# Ctrl_Sist_de_seguridad_SCH.net
KiCad netlist of a schematic drawn in Altium Designer
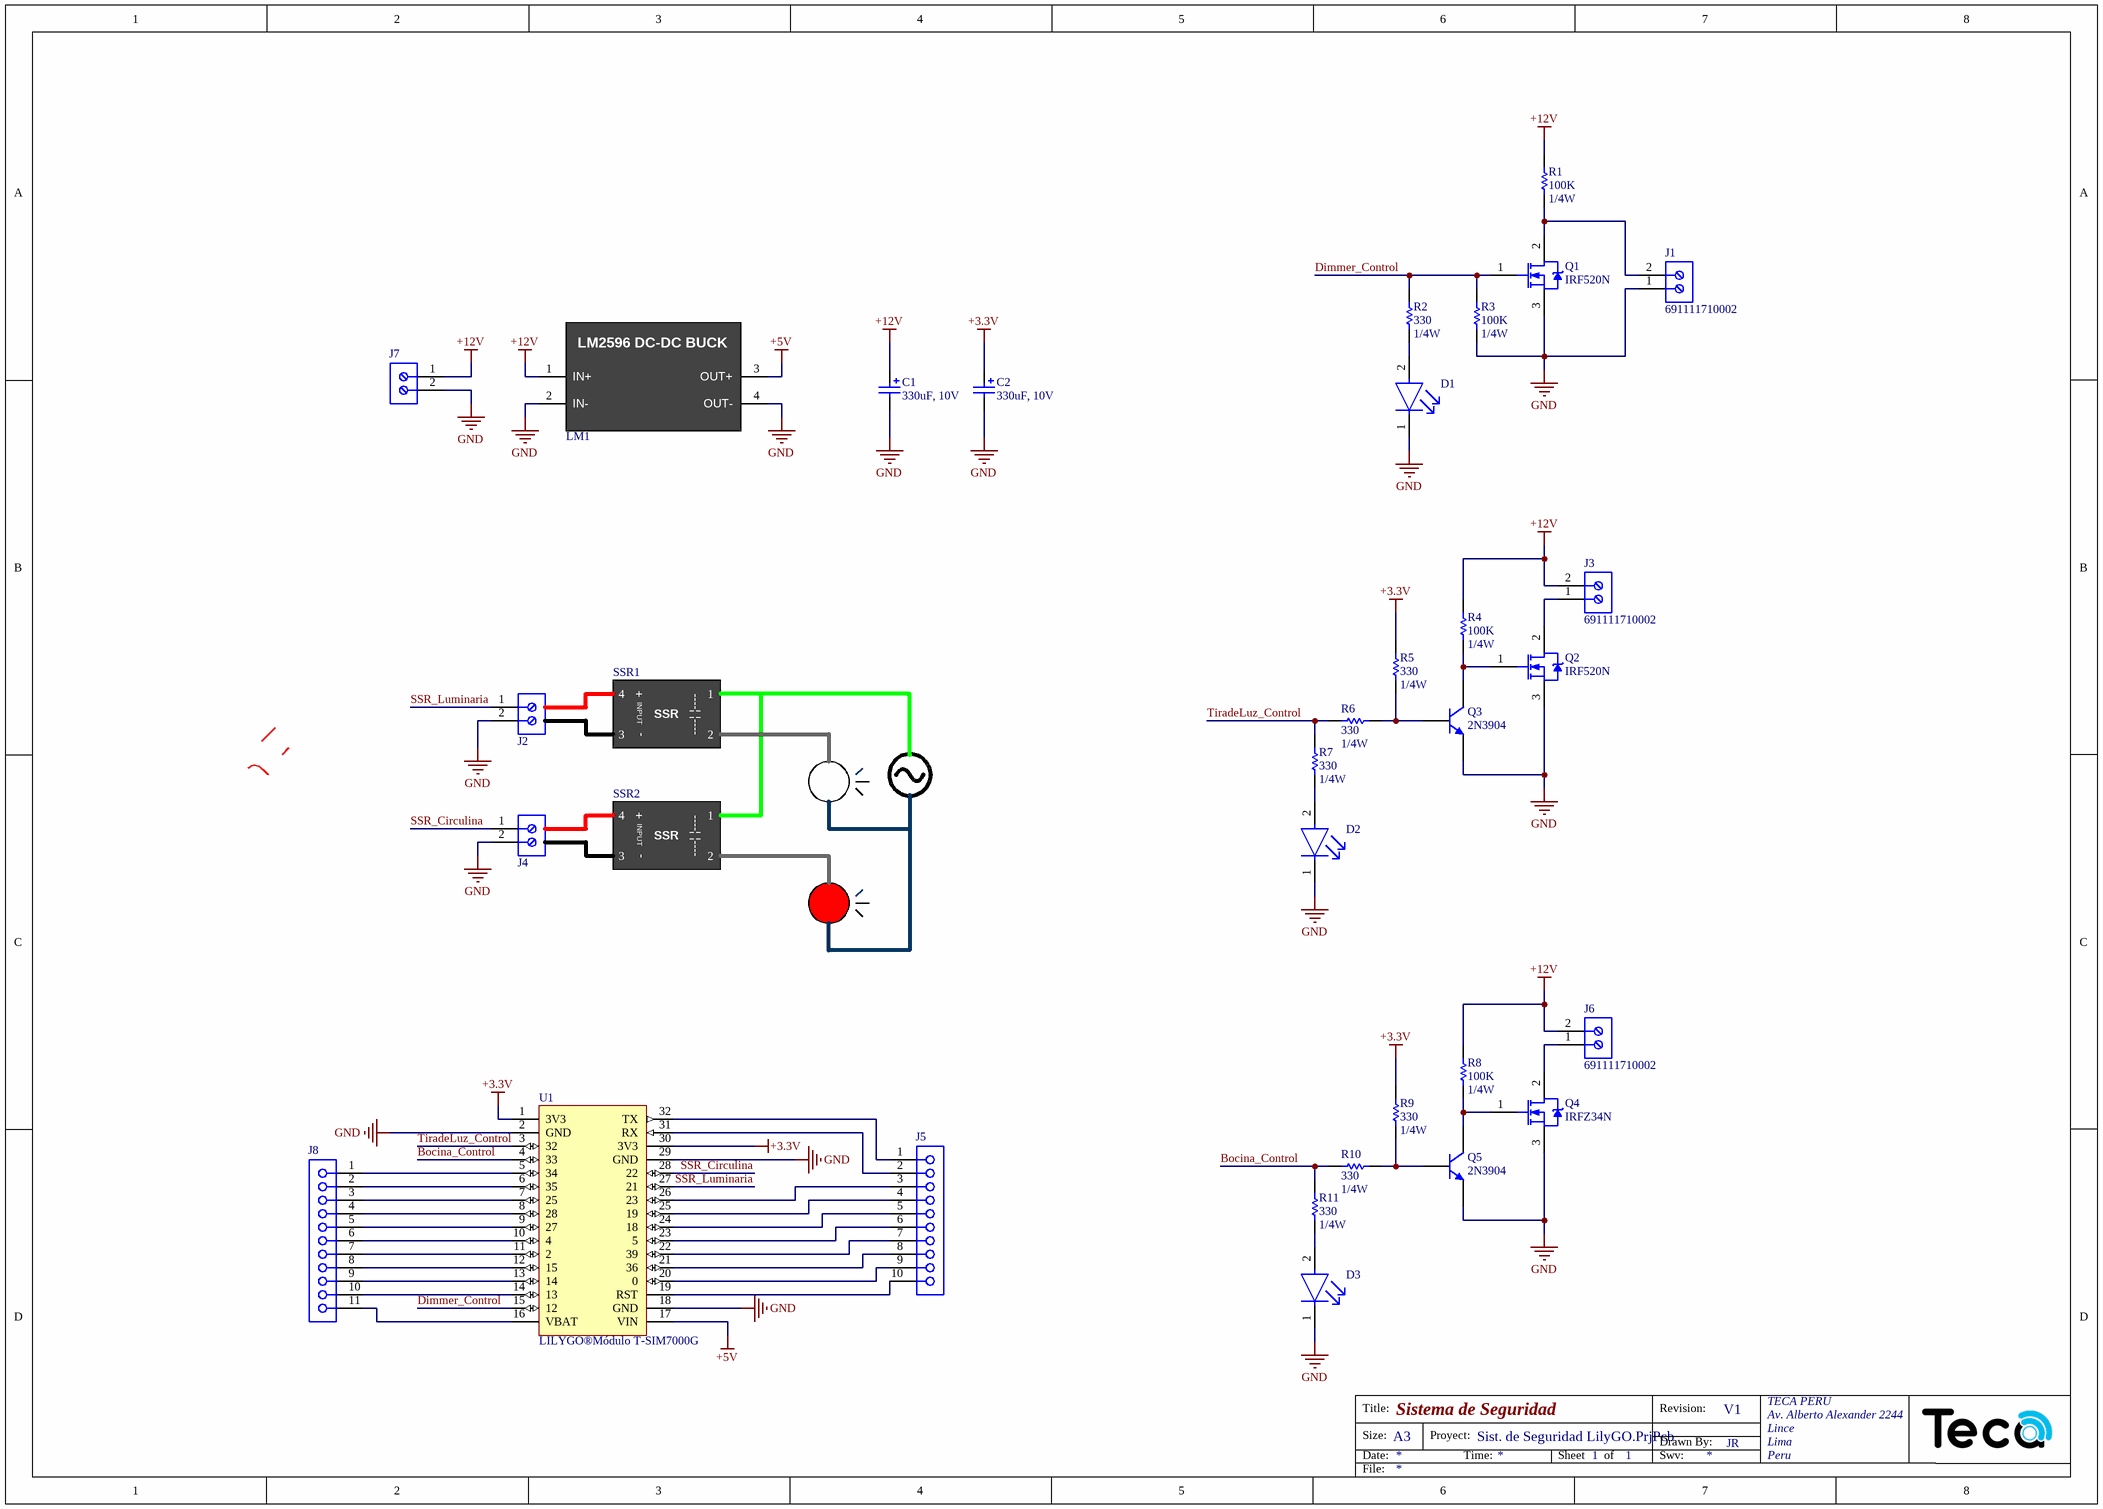
[diagram p0: Ctrl Sist de seguridad SCH.SchDoc]

(export (version "E")
  (design (tool "Eeschema 10.0.6"))
  (components
    (comp (ref "C1")
      (value "330uF, 10V")
      (footprint "WCAP-ATLI_D8H11.5")
      (description "WCAP-ATLI Aluminum Electrolytic Capacitor, Radial, THT, D8xH11.5mm, 330uF, 10V")
      (fields
        (field (name "MANUFACTURER PART NUMBER") "860080274009")
        (field (name "MANUFACTURER") "Wurth Elektronik")
      )
      (libsource (lib "WCAP-ATLI Aluminion Electrolytic Capacitors") (part "860080274009"))
    )
    (comp (ref "C2")
      (value "330uF, 10V")
      (footprint "WCAP-ATLI_D8H11.5")
      (description "WCAP-ATLI Aluminum Electrolytic Capacitor, Radial, THT, D8xH11.5mm, 330uF, 10V")
      (fields
        (field (name "MANUFACTURER PART NUMBER") "860080274009")
        (field (name "MANUFACTURER") "Wurth Elektronik")
      )
      (libsource (lib "WCAP-ATLI Aluminion Electrolytic Capacitors") (part "860080274009"))
    )
    (comp (ref "D1")
      (value "HLMP-4700")
      (footprint "FP-HLMP-4700-MFG")
      (description "LED RED DIFFUSED T-1 3/4 T/H")
      (fields
        (field (name "OCTOPART") "https://octopart.com/hlmp-4700-broadcom-71130526")
        (field (name "MANUFACTURER") "Broadcom")
      )
      (libsource (lib "Altium Content Vault") (part "8706943c75ba83719d021d2fdc84c58"))
    )
    (comp (ref "D2")
      (value "HLMP-4700")
      (footprint "FP-HLMP-4700-MFG")
      (description "LED RED DIFFUSED T-1 3/4 T/H")
      (fields
        (field (name "OCTOPART") "https://octopart.com/hlmp-4700-broadcom-71130526")
        (field (name "MANUFACTURER") "Broadcom")
      )
      (libsource (lib "Altium Content Vault") (part "8706943c75ba83719d021d2fdc84c58"))
    )
    (comp (ref "D3")
      (value "HLMP-4700")
      (footprint "FP-HLMP-4700-MFG")
      (description "LED RED DIFFUSED T-1 3/4 T/H")
      (fields
        (field (name "OCTOPART") "https://octopart.com/hlmp-4700-broadcom-71130526")
        (field (name "MANUFACTURER") "Broadcom")
      )
      (libsource (lib "Altium Content Vault") (part "8706943c75ba83719d021d2fdc84c58"))
    )
    (comp (ref "J1")
      (value "691111710002")
      (footprint "691111710002")
      (description "WR-TBL Serie 111 Horizontal Entry Modular, Pressure Clamp, THT, pitch 5mm, 2p")
      (fields (field (name "MANUFACTURER") "Wurth Elektronik"))
      (libsource (lib "WR-TBL Terminal Blocks") (part "691111710002"))
    )
    (comp (ref "J2")
      (value "691111710002")
      (footprint "691111710002")
      (description "WR-TBL Serie 111 Horizontal Entry Modular, Pressure Clamp, THT, pitch 5mm, 2p")
      (fields (field (name "MANUFACTURER") "Wurth Elektronik"))
      (libsource (lib "WR-TBL Terminal Blocks") (part "691111710002"))
    )
    (comp (ref "J3")
      (value "691111710002")
      (footprint "691111710002")
      (description "WR-TBL Serie 111 Horizontal Entry Modular, Pressure Clamp, THT, pitch 5mm, 2p")
      (fields (field (name "MANUFACTURER") "Wurth Elektronik"))
      (libsource (lib "WR-TBL Terminal Blocks") (part "691111710002"))
    )
    (comp (ref "J4")
      (value "691111710002")
      (footprint "691111710002")
      (description "WR-TBL Serie 111 Horizontal Entry Modular, Pressure Clamp, THT, pitch 5mm, 2p")
      (fields (field (name "MANUFACTURER") "Wurth Elektronik"))
      (libsource (lib "WR-TBL Terminal Blocks") (part "691111710002"))
    )
    (comp (ref "J5")
      (value "61301011821")
      (footprint "61301011821")
      (description "WR-PHD Socket Header, THT, pitch 2.54mm, Single Row, Vertical, 10p")
      (fields (field (name "MANUFACTURER") "Wurth Elektronik"))
      (libsource (lib "WE-WR PHD Conectors") (part "61301011821"))
    )
    (comp (ref "J6")
      (value "691111710002")
      (footprint "691111710002")
      (description "WR-TBL Serie 111 Horizontal Entry Modular, Pressure Clamp, THT, pitch 5mm, 2p")
      (fields (field (name "MANUFACTURER") "Wurth Elektronik"))
      (libsource (lib "WR-TBL Terminal Blocks") (part "691111710002"))
    )
    (comp (ref "J7")
      (value "691111710002")
      (footprint "691111710002")
      (description "WR-TBL Serie 111 Horizontal Entry Modular, Pressure Clamp, THT, pitch 5mm, 2p")
      (fields (field (name "MANUFACTURER") "Wurth Elektronik"))
      (libsource (lib "WR-TBL Terminal Blocks") (part "691111710002"))
    )
    (comp (ref "J8")
      (value "61301111821")
      (footprint "61301111821")
      (description "WR-PHD Socket Header, THT, pitch 2.54mm, Single Row, Vertical, 11p")
      (fields (field (name "MANUFACTURER") "Wurth Elektronik"))
      (libsource (lib "WE-WR PHD Conectors") (part "61301111821"))
    )
    (comp (ref "LM1") (value "LM2596?") (footprint "LM2596") (libsource (lib "Modulos") (part "LM2596?")))
    (comp (ref "Q1")
      (value "IRF520N")
      (footprint "INTR-TO-220AB-3")
      (description "HEXFET(R) Power MOSFET, 100 V, 9.7 A, 0.2 Ohm, -55 to 175 degC, 3-Pin FM (TO-220AB), RoHS, Tube")
      (fields (field (name "MANUFACTURER") "International Rectifier"))
      (libsource (lib "Altium Content Vault") (part "NEMOS-GDS-3_B"))
    )
    (comp (ref "Q2")
      (value "IRF520N")
      (footprint "INTR-TO-220AB-3")
      (description "HEXFET(R) Power MOSFET, 100 V, 9.7 A, 0.2 Ohm, -55 to 175 degC, 3-Pin FM (TO-220AB), RoHS, Tube")
      (fields (field (name "MANUFACTURER") "International Rectifier"))
      (libsource (lib "Altium Content Vault") (part "NEMOS-GDS-3_B"))
    )
    (comp (ref "Q3")
      (value "2N3904")
      (footprint "TO-92A")
      (description "NPN General Purpose Amplifier")
      (fields (field (name "PUBLISHER") "Altium Limited"))
      (libsource (lib "Miscellaneous Devices") (part "2N3904"))
    )
    (comp (ref "Q4")
      (value "IRFZ34N")
      (footprint "INTR-TO-220AB-3")
      (description "HEXFET(R) Power MOSFET, 100 V, 9.7 A, 0.2 Ohm, -55 to 175 degC, 3-Pin FM (TO-220AB), RoHS, Tube")
      (fields (field (name "MANUFACTURER") "International Rectifier"))
      (libsource (lib "Altium Content Vault") (part "NEMOS-GDS-3_B"))
    )
    (comp (ref "Q5")
      (value "2N3904")
      (footprint "TO-92A")
      (description "NPN General Purpose Amplifier")
      (fields (field (name "PUBLISHER") "Altium Limited"))
      (libsource (lib "Miscellaneous Devices") (part "2N3904"))
    )
    (comp (ref "R1")
      (value "Resistor 1/4W")
      (footprint "RESISTOR 1/4W - 10mm")
      (fields
        (field (name "TOLERANCE") "1%")
        (field (name "RESISTANCE") "100K")
        (field (name "POWER RATING") "1/4W")
      )
      (libsource (lib "Resistencias THT") (part "Resistor 1/4W"))
    )
    (comp (ref "R2")
      (value "Resistor 1/4W")
      (footprint "RESISTOR 1/4W - 10mm")
      (fields
        (field (name "TOLERANCE") "1%")
        (field (name "RESISTANCE") "330")
        (field (name "POWER RATING") "1/4W")
      )
      (libsource (lib "Resistencias THT") (part "Resistor 1/4W"))
    )
    (comp (ref "R3")
      (value "Resistor 1/4W")
      (footprint "RESISTOR 1/4W - 10mm")
      (fields
        (field (name "TOLERANCE") "1%")
        (field (name "RESISTANCE") "100K")
        (field (name "POWER RATING") "1/4W")
      )
      (libsource (lib "Resistencias THT") (part "Resistor 1/4W"))
    )
    (comp (ref "R4")
      (value "Resistor 1/4W")
      (footprint "RESISTOR 1/4W - 10mm")
      (fields
        (field (name "TOLERANCE") "1%")
        (field (name "RESISTANCE") "100K")
        (field (name "POWER RATING") "1/4W")
      )
      (libsource (lib "Resistencias THT") (part "Resistor 1/4W"))
    )
    (comp (ref "R5")
      (value "Resistor 1/4W")
      (footprint "RESISTOR 1/4W - 10mm")
      (fields
        (field (name "TOLERANCE") "1%")
        (field (name "RESISTANCE") "330")
        (field (name "POWER RATING") "1/4W")
      )
      (libsource (lib "Resistencias THT") (part "Resistor 1/4W"))
    )
    (comp (ref "R6")
      (value "Resistor 1/4W")
      (footprint "RESISTOR 1/4W - 10mm")
      (fields
        (field (name "TOLERANCE") "1%")
        (field (name "RESISTANCE") "330")
        (field (name "POWER RATING") "1/4W")
      )
      (libsource (lib "Resistencias THT") (part "Resistor 1/4W"))
    )
    (comp (ref "R7")
      (value "Resistor 1/4W")
      (footprint "RESISTOR 1/4W - 10mm")
      (fields
        (field (name "TOLERANCE") "1%")
        (field (name "RESISTANCE") "330")
        (field (name "POWER RATING") "1/4W")
      )
      (libsource (lib "Resistencias THT") (part "Resistor 1/4W"))
    )
    (comp (ref "R8")
      (value "Resistor 1/4W")
      (footprint "RESISTOR 1/4W - 10mm")
      (fields
        (field (name "TOLERANCE") "1%")
        (field (name "RESISTANCE") "100K")
        (field (name "POWER RATING") "1/4W")
      )
      (libsource (lib "Resistencias THT") (part "Resistor 1/4W"))
    )
    (comp (ref "R9")
      (value "Resistor 1/4W")
      (footprint "RESISTOR 1/4W - 10mm")
      (fields
        (field (name "TOLERANCE") "1%")
        (field (name "RESISTANCE") "330")
        (field (name "POWER RATING") "1/4W")
      )
      (libsource (lib "Resistencias THT") (part "Resistor 1/4W"))
    )
    (comp (ref "R10")
      (value "Resistor 1/4W")
      (footprint "RESISTOR 1/4W - 10mm")
      (fields
        (field (name "TOLERANCE") "1%")
        (field (name "RESISTANCE") "330")
        (field (name "POWER RATING") "1/4W")
      )
      (libsource (lib "Resistencias THT") (part "Resistor 1/4W"))
    )
    (comp (ref "R11")
      (value "Resistor 1/4W")
      (footprint "RESISTOR 1/4W - 10mm")
      (fields
        (field (name "TOLERANCE") "1%")
        (field (name "RESISTANCE") "330")
        (field (name "POWER RATING") "1/4W")
      )
      (libsource (lib "Resistencias THT") (part "Resistor 1/4W"))
    )
    (comp (ref "SSR1") (value "SSR") (footprint "SSR Generic") (libsource (lib "Modulos") (part "SSR")))
    (comp (ref "SSR2") (value "SSR") (footprint "SSR Generic") (libsource (lib "Modulos") (part "SSR")))
    (comp (ref "U1")
      (value "LILYGO®Módulo T-SIM7000G")
      (footprint "LILYGO T-SIM7000G")
      (libsource (lib "Modulos") (part "LILYGO®Módulo T-SIM7000G"))
    )
  )
  (nets
    (net (code "1") (name "+3.3V") (class "Default")
      (node (ref "C2") (pin "1") (pinfunction "P_1") (pintype "passive"))
      (node (ref "R5") (pin "2") (pinfunction "2_2") (pintype "passive"))
      (node (ref "R9") (pin "2") (pinfunction "2_2") (pintype "passive"))
      (node (ref "U1") (pin "1") (pinfunction "3V3_1") (pintype "power_in"))
      (node (ref "U1") (pin "30") (pinfunction "3V3_30") (pintype "power_in"))
    )
    (net (code "2") (name "+5V") (class "Default")
      (node (ref "LM1") (pin "3") (pinfunction "OUT+_3") (pintype "passive"))
      (node (ref "U1") (pin "17") (pinfunction "VIN_17") (pintype "power_in"))
    )
    (net (code "3") (name "+12V") (class "Default")
      (node (ref "C1") (pin "1") (pinfunction "P_1") (pintype "passive"))
      (node (ref "J3") (pin "2") (pinfunction "2_2") (pintype "passive"))
      (node (ref "J6") (pin "2") (pinfunction "2_2") (pintype "passive"))
      (node (ref "J7") (pin "1") (pinfunction "1_1") (pintype "passive"))
      (node (ref "LM1") (pin "1") (pinfunction "IN+_1") (pintype "passive"))
      (node (ref "R1") (pin "2") (pinfunction "2_2") (pintype "passive"))
      (node (ref "R4") (pin "2") (pinfunction "2_2") (pintype "passive"))
      (node (ref "R8") (pin "2") (pinfunction "2_2") (pintype "passive"))
    )
    (net (code "4") (name "/Bocina_Control") (class "Default")
      (node (ref "R10") (pin "2") (pinfunction "2_2") (pintype "passive"))
      (node (ref "R11") (pin "1") (pinfunction "1_1") (pintype "passive"))
      (node (ref "U1") (pin "4") (pinfunction "33_4") (pintype "bidirectional"))
    )
    (net (code "5") (name "/Dimmer_Control") (class "Default")
      (node (ref "Q1") (pin "1") (pinfunction "G_1") (pintype "passive"))
      (node (ref "R2") (pin "2") (pinfunction "2_2") (pintype "passive"))
      (node (ref "R3") (pin "2") (pinfunction "2_2") (pintype "passive"))
      (node (ref "U1") (pin "15") (pinfunction "12_15") (pintype "bidirectional"))
    )
    (net (code "6") (name "/SSR_Circulina") (class "Default")
      (node (ref "J4") (pin "1") (pinfunction "1_1") (pintype "passive"))
      (node (ref "U1") (pin "28") (pinfunction "22_28") (pintype "bidirectional"))
    )
    (net (code "7") (name "/SSR_Luminaria") (class "Default")
      (node (ref "J2") (pin "1") (pinfunction "1_1") (pintype "passive"))
      (node (ref "U1") (pin "27") (pinfunction "21_27") (pintype "bidirectional"))
    )
    (net (code "8") (name "/TiradeLuz_Control") (class "Default")
      (node (ref "R6") (pin "2") (pinfunction "2_2") (pintype "passive"))
      (node (ref "R7") (pin "1") (pinfunction "1_1") (pintype "passive"))
      (node (ref "U1") (pin "3") (pinfunction "32_3") (pintype "bidirectional"))
    )
    (net (code "9") (name "GND") (class "Default")
      (node (ref "C1") (pin "2") (pinfunction "N_2") (pintype "passive"))
      (node (ref "C2") (pin "2") (pinfunction "N_2") (pintype "passive"))
      (node (ref "D1") (pin "1") (pinfunction "C_1") (pintype "passive"))
      (node (ref "D2") (pin "1") (pinfunction "C_1") (pintype "passive"))
      (node (ref "D3") (pin "1") (pinfunction "C_1") (pintype "passive"))
      (node (ref "J1") (pin "1") (pinfunction "1_1") (pintype "passive"))
      (node (ref "J2") (pin "2") (pinfunction "2_2") (pintype "passive"))
      (node (ref "J4") (pin "2") (pinfunction "2_2") (pintype "passive"))
      (node (ref "J7") (pin "2") (pinfunction "2_2") (pintype "passive"))
      (node (ref "LM1") (pin "2") (pinfunction "IN-_2") (pintype "passive"))
      (node (ref "LM1") (pin "4") (pinfunction "OUT-_4") (pintype "passive"))
      (node (ref "Q1") (pin "3") (pinfunction "S_3") (pintype "passive"))
      (node (ref "Q2") (pin "3") (pinfunction "S_3") (pintype "passive"))
      (node (ref "Q3") (pin "1") (pinfunction "E_1") (pintype "passive"))
      (node (ref "Q4") (pin "3") (pinfunction "S_3") (pintype "passive"))
      (node (ref "Q5") (pin "1") (pinfunction "E_1") (pintype "passive"))
      (node (ref "R3") (pin "1") (pinfunction "1_1") (pintype "passive"))
      (node (ref "U1") (pin "18") (pinfunction "GND_18") (pintype "power_in"))
      (node (ref "U1") (pin "2") (pinfunction "GND_2") (pintype "power_in"))
      (node (ref "U1") (pin "29") (pinfunction "GND_29") (pintype "power_in"))
    )
    (net (code "10") (name "Net-(D1-A)") (class "Default")
      (node (ref "D1") (pin "2") (pinfunction "A_2") (pintype "passive"))
      (node (ref "R2") (pin "1") (pinfunction "1_1") (pintype "passive"))
    )
    (net (code "11") (name "Net-(D2-A)") (class "Default")
      (node (ref "D2") (pin "2") (pinfunction "A_2") (pintype "passive"))
      (node (ref "R7") (pin "2") (pinfunction "2_2") (pintype "passive"))
    )
    (net (code "12") (name "Net-(D3-A)") (class "Default")
      (node (ref "D3") (pin "2") (pinfunction "A_2") (pintype "passive"))
      (node (ref "R11") (pin "2") (pinfunction "2_2") (pintype "passive"))
    )
    (net (code "13") (name "Net-(Q1-D)") (class "Default")
      (node (ref "J1") (pin "2") (pinfunction "2_2") (pintype "passive"))
      (node (ref "Q1") (pin "2") (pinfunction "D_2") (pintype "passive"))
      (node (ref "R1") (pin "1") (pinfunction "1_1") (pintype "passive"))
    )
    (net (code "14") (name "Net-(Q2-D)") (class "Default")
      (node (ref "J3") (pin "1") (pinfunction "1_1") (pintype "passive"))
      (node (ref "Q2") (pin "2") (pinfunction "D_2") (pintype "passive"))
    )
    (net (code "15") (name "Net-(Q2-G)") (class "Default")
      (node (ref "Q2") (pin "1") (pinfunction "G_1") (pintype "passive"))
      (node (ref "Q3") (pin "3") (pinfunction "C_3") (pintype "passive"))
      (node (ref "R4") (pin "1") (pinfunction "1_1") (pintype "passive"))
    )
    (net (code "16") (name "Net-(Q3-B)") (class "Default")
      (node (ref "Q3") (pin "2") (pinfunction "B_2") (pintype "passive"))
      (node (ref "R5") (pin "1") (pinfunction "1_1") (pintype "passive"))
      (node (ref "R6") (pin "1") (pinfunction "1_1") (pintype "passive"))
    )
    (net (code "17") (name "Net-(Q4-D)") (class "Default")
      (node (ref "J6") (pin "1") (pinfunction "1_1") (pintype "passive"))
      (node (ref "Q4") (pin "2") (pinfunction "D_2") (pintype "passive"))
    )
    (net (code "18") (name "Net-(Q4-G)") (class "Default")
      (node (ref "Q4") (pin "1") (pinfunction "G_1") (pintype "passive"))
      (node (ref "Q5") (pin "3") (pinfunction "C_3") (pintype "passive"))
      (node (ref "R8") (pin "1") (pinfunction "1_1") (pintype "passive"))
    )
    (net (code "19") (name "Net-(Q5-B)") (class "Default")
      (node (ref "Q5") (pin "2") (pinfunction "B_2") (pintype "passive"))
      (node (ref "R10") (pin "1") (pinfunction "1_1") (pintype "passive"))
      (node (ref "R9") (pin "1") (pinfunction "1_1") (pintype "passive"))
    )
    (net (code "20") (name "Net-(U1-0)") (class "Default")
      (node (ref "J5") (pin "9") (pinfunction "9_9") (pintype "passive"))
      (node (ref "U1") (pin "20") (pinfunction "0_20") (pintype "bidirectional"))
    )
    (net (code "21") (name "Net-(U1-2)") (class "Default")
      (node (ref "J8") (pin "7") (pinfunction "7_7") (pintype "passive"))
      (node (ref "U1") (pin "11") (pinfunction "2_11") (pintype "bidirectional"))
    )
    (net (code "22") (name "Net-(U1-4)") (class "Default")
      (node (ref "J8") (pin "6") (pinfunction "6_6") (pintype "passive"))
      (node (ref "U1") (pin "10") (pinfunction "4_10") (pintype "bidirectional"))
    )
    (net (code "23") (name "Net-(U1-5)") (class "Default")
      (node (ref "J5") (pin "6") (pinfunction "6_6") (pintype "passive"))
      (node (ref "U1") (pin "23") (pinfunction "5_23") (pintype "bidirectional"))
    )
    (net (code "24") (name "Net-(U1-13)") (class "Default")
      (node (ref "J8") (pin "10") (pinfunction "10_10") (pintype "passive"))
      (node (ref "U1") (pin "14") (pinfunction "13_14") (pintype "bidirectional"))
    )
    (net (code "25") (name "Net-(U1-14)") (class "Default")
      (node (ref "J8") (pin "9") (pinfunction "9_9") (pintype "passive"))
      (node (ref "U1") (pin "13") (pinfunction "14_13") (pintype "bidirectional"))
    )
    (net (code "26") (name "Net-(U1-15)") (class "Default")
      (node (ref "J8") (pin "8") (pinfunction "8_8") (pintype "passive"))
      (node (ref "U1") (pin "12") (pinfunction "15_12") (pintype "bidirectional"))
    )
    (net (code "27") (name "Net-(U1-18)") (class "Default")
      (node (ref "J5") (pin "5") (pinfunction "5_5") (pintype "passive"))
      (node (ref "U1") (pin "24") (pinfunction "18_24") (pintype "bidirectional"))
    )
    (net (code "28") (name "Net-(U1-19)") (class "Default")
      (node (ref "J5") (pin "4") (pinfunction "4_4") (pintype "passive"))
      (node (ref "U1") (pin "25") (pinfunction "19_25") (pintype "bidirectional"))
    )
    (net (code "29") (name "Net-(U1-23)") (class "Default")
      (node (ref "J5") (pin "3") (pinfunction "3_3") (pintype "passive"))
      (node (ref "U1") (pin "26") (pinfunction "23_26") (pintype "bidirectional"))
    )
    (net (code "30") (name "Net-(U1-25)") (class "Default")
      (node (ref "J8") (pin "3") (pinfunction "3_3") (pintype "passive"))
      (node (ref "U1") (pin "7") (pinfunction "25_7") (pintype "bidirectional"))
    )
    (net (code "31") (name "Net-(U1-27)") (class "Default")
      (node (ref "J8") (pin "5") (pinfunction "5_5") (pintype "passive"))
      (node (ref "U1") (pin "9") (pinfunction "27_9") (pintype "bidirectional"))
    )
    (net (code "32") (name "Net-(U1-28)") (class "Default")
      (node (ref "J8") (pin "4") (pinfunction "4_4") (pintype "passive"))
      (node (ref "U1") (pin "8") (pinfunction "28_8") (pintype "bidirectional"))
    )
    (net (code "33") (name "Net-(U1-34)") (class "Default")
      (node (ref "J8") (pin "1") (pinfunction "1_1") (pintype "passive"))
      (node (ref "U1") (pin "5") (pinfunction "34_5") (pintype "bidirectional"))
    )
    (net (code "34") (name "Net-(U1-35)") (class "Default")
      (node (ref "J8") (pin "2") (pinfunction "2_2") (pintype "passive"))
      (node (ref "U1") (pin "6") (pinfunction "35_6") (pintype "bidirectional"))
    )
    (net (code "35") (name "Net-(U1-36)") (class "Default")
      (node (ref "J5") (pin "8") (pinfunction "8_8") (pintype "passive"))
      (node (ref "U1") (pin "21") (pinfunction "36_21") (pintype "bidirectional"))
    )
    (net (code "36") (name "Net-(U1-39)") (class "Default")
      (node (ref "J5") (pin "7") (pinfunction "7_7") (pintype "passive"))
      (node (ref "U1") (pin "22") (pinfunction "39_22") (pintype "bidirectional"))
    )
    (net (code "37") (name "Net-(U1-RST)") (class "Default")
      (node (ref "J5") (pin "10") (pinfunction "10_10") (pintype "passive"))
      (node (ref "U1") (pin "19") (pinfunction "RST_19") (pintype "passive"))
    )
    (net (code "38") (name "Net-(U1-RX)") (class "Default")
      (node (ref "J5") (pin "2") (pinfunction "2_2") (pintype "passive"))
      (node (ref "U1") (pin "31") (pinfunction "RX_31") (pintype "input"))
    )
    (net (code "39") (name "Net-(U1-TX)") (class "Default")
      (node (ref "J5") (pin "1") (pinfunction "1_1") (pintype "passive"))
      (node (ref "U1") (pin "32") (pinfunction "TX_32") (pintype "output"))
    )
    (net (code "40") (name "Net-(U1-VBAT)") (class "Default")
      (node (ref "J8") (pin "11") (pinfunction "11_11") (pintype "passive"))
      (node (ref "U1") (pin "16") (pinfunction "VBAT_16") (pintype "power_in"))
    )
  )
)
